# FEU31_Part2.net
KiCad netlist of a schematic drawn in Altium Designer
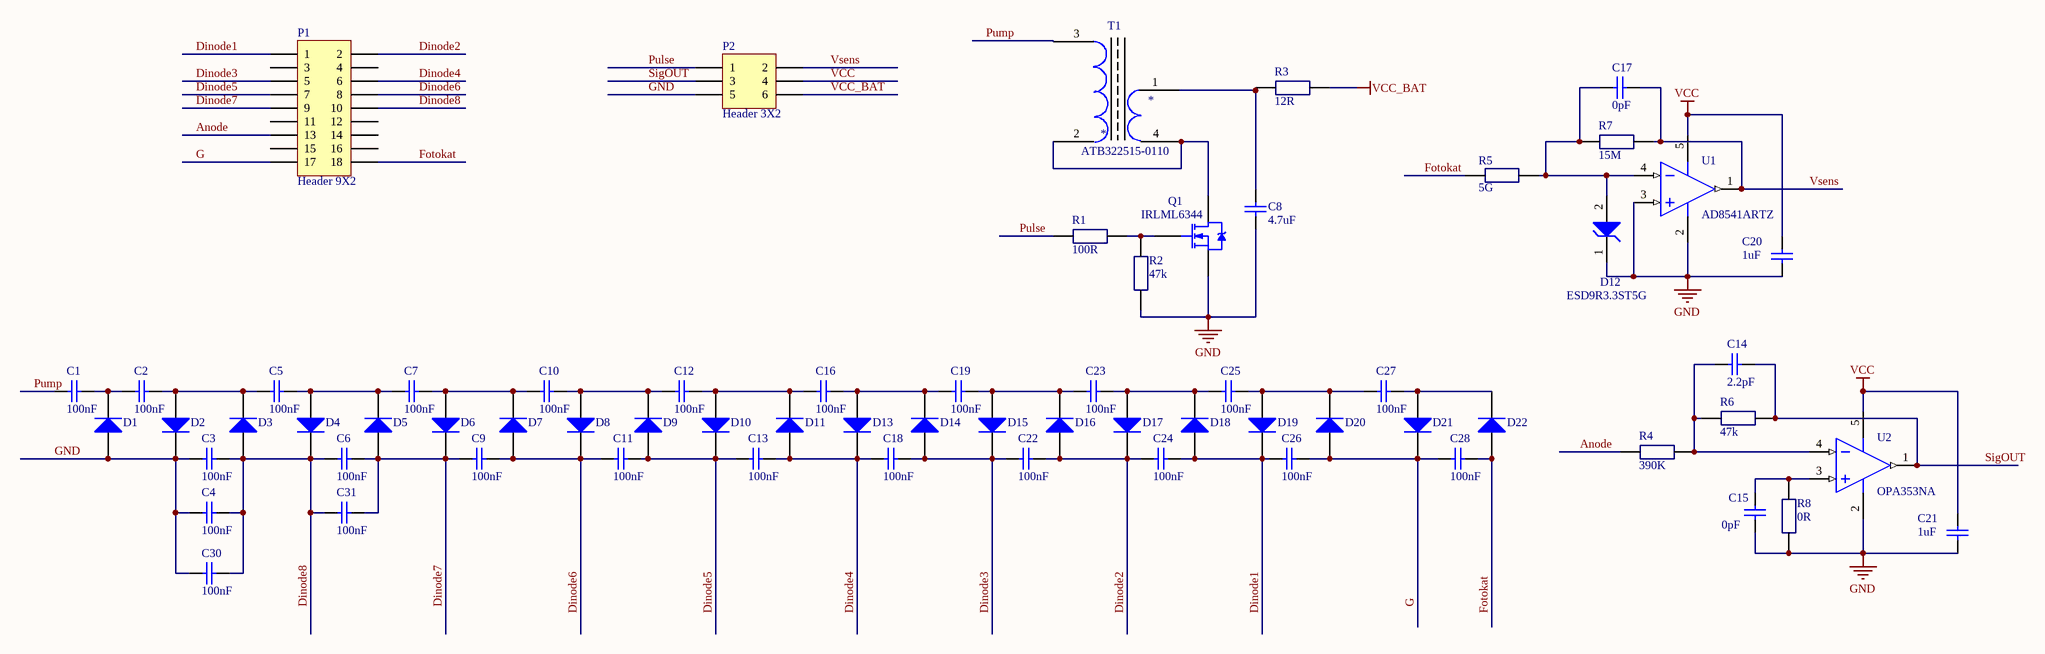
[diagram p0: FEU31_Part2.SchDoc]

(export (version "E")
  (design (tool "Eeschema 10.0.6"))
  (components
    (comp (ref "C1")
      (value "100nF")
      (footprint "Miscellaneous Devices:C1206")
      (description "Capacitor (Semiconductor SIM Model)")
      (fields (field (name "PUBLISHER") "Altium Limited"))
      (libsource (lib "Miscellaneous Devices") (part "Cap Semi"))
    )
    (comp (ref "C2")
      (value "100nF")
      (footprint "Miscellaneous Devices:C1206")
      (description "Capacitor (Semiconductor SIM Model)")
      (fields (field (name "PUBLISHER") "Altium Limited"))
      (libsource (lib "Miscellaneous Devices") (part "Cap Semi"))
    )
    (comp (ref "C3")
      (value "100nF")
      (footprint "Miscellaneous Devices:C1206")
      (description "Capacitor (Semiconductor SIM Model)")
      (fields (field (name "PUBLISHER") "Altium Limited"))
      (libsource (lib "Miscellaneous Devices") (part "Cap Semi"))
    )
    (comp (ref "C4")
      (value "100nF")
      (footprint "Miscellaneous Devices:C1206")
      (description "Capacitor (Semiconductor SIM Model)")
      (fields (field (name "PUBLISHER") "Altium Limited"))
      (libsource (lib "Miscellaneous Devices") (part "Cap Semi"))
    )
    (comp (ref "C5")
      (value "100nF")
      (footprint "Miscellaneous Devices:C1206")
      (description "Capacitor (Semiconductor SIM Model)")
      (fields (field (name "PUBLISHER") "Altium Limited"))
      (libsource (lib "Miscellaneous Devices") (part "Cap Semi"))
    )
    (comp (ref "C6")
      (value "100nF")
      (footprint "Miscellaneous Devices:C1206")
      (description "Capacitor (Semiconductor SIM Model)")
      (fields (field (name "PUBLISHER") "Altium Limited"))
      (libsource (lib "Miscellaneous Devices") (part "Cap Semi"))
    )
    (comp (ref "C7")
      (value "100nF")
      (footprint "Miscellaneous Devices:C1206")
      (description "Capacitor (Semiconductor SIM Model)")
      (fields (field (name "PUBLISHER") "Altium Limited"))
      (libsource (lib "Miscellaneous Devices") (part "Cap Semi"))
    )
    (comp (ref "C8")
      (value "4.7uF")
      (footprint "Miscellaneous Devices:C1206")
      (description "Capacitor (Semiconductor SIM Model)")
      (fields (field (name "PUBLISHER") "Altium Limited"))
      (libsource (lib "Miscellaneous Devices") (part "Cap Semi"))
    )
    (comp (ref "C9")
      (value "100nF")
      (footprint "Miscellaneous Devices:C1206")
      (description "Capacitor (Semiconductor SIM Model)")
      (fields (field (name "PUBLISHER") "Altium Limited"))
      (libsource (lib "Miscellaneous Devices") (part "Cap Semi"))
    )
    (comp (ref "C10")
      (value "100nF")
      (footprint "Miscellaneous Devices:C1206")
      (description "Capacitor (Semiconductor SIM Model)")
      (fields (field (name "PUBLISHER") "Altium Limited"))
      (libsource (lib "Miscellaneous Devices") (part "Cap Semi"))
    )
    (comp (ref "C11")
      (value "100nF")
      (footprint "Miscellaneous Devices:C1206")
      (description "Capacitor (Semiconductor SIM Model)")
      (fields (field (name "PUBLISHER") "Altium Limited"))
      (libsource (lib "Miscellaneous Devices") (part "Cap Semi"))
    )
    (comp (ref "C12")
      (value "100nF")
      (footprint "Miscellaneous Devices:C1206")
      (description "Capacitor (Semiconductor SIM Model)")
      (fields (field (name "PUBLISHER") "Altium Limited"))
      (libsource (lib "Miscellaneous Devices") (part "Cap Semi"))
    )
    (comp (ref "C13")
      (value "100nF")
      (footprint "Miscellaneous Devices:C1206")
      (description "Capacitor (Semiconductor SIM Model)")
      (fields (field (name "PUBLISHER") "Altium Limited"))
      (libsource (lib "Miscellaneous Devices") (part "Cap Semi"))
    )
    (comp (ref "C14")
      (value "2.2pF")
      (footprint "1608[0603]")
      (description "Capacitor (Semiconductor SIM Model)")
      (fields (field (name "PUBLISHER") "Altium Limited"))
      (libsource (lib "Miscellaneous Devices") (part "Cap Semi"))
    )
    (comp (ref "C15")
      (value "0pF")
      (footprint "1608[0603]_CAP")
      (description "Capacitor (Semiconductor SIM Model)")
      (fields (field (name "PUBLISHER") "Altium Limited"))
      (libsource (lib "Miscellaneous Devices") (part "Cap Semi"))
    )
    (comp (ref "C16")
      (value "100nF")
      (footprint "Miscellaneous Devices:C1206")
      (description "Capacitor (Semiconductor SIM Model)")
      (fields (field (name "PUBLISHER") "Altium Limited"))
      (libsource (lib "Miscellaneous Devices") (part "Cap Semi"))
    )
    (comp (ref "C17")
      (value "0pF")
      (footprint "1608[0603]")
      (description "Capacitor (Semiconductor SIM Model)")
      (fields (field (name "PUBLISHER") "Altium Limited"))
      (libsource (lib "Miscellaneous Devices") (part "Cap Semi"))
    )
    (comp (ref "C18")
      (value "100nF")
      (footprint "Miscellaneous Devices:C1206")
      (description "Capacitor (Semiconductor SIM Model)")
      (fields (field (name "PUBLISHER") "Altium Limited"))
      (libsource (lib "Miscellaneous Devices") (part "Cap Semi"))
    )
    (comp (ref "C19")
      (value "100nF")
      (footprint "Miscellaneous Devices:C1206")
      (description "Capacitor (Semiconductor SIM Model)")
      (fields (field (name "PUBLISHER") "Altium Limited"))
      (libsource (lib "Miscellaneous Devices") (part "Cap Semi"))
    )
    (comp (ref "C20")
      (value "1uF")
      (footprint "1608[0603]_CAP")
      (description "Capacitor (Semiconductor SIM Model)")
      (fields (field (name "PUBLISHER") "Altium Limited"))
      (libsource (lib "Miscellaneous Devices") (part "Cap Semi"))
    )
    (comp (ref "C21")
      (value "1uF")
      (footprint "1608[0603]_CAP")
      (description "Capacitor (Semiconductor SIM Model)")
      (fields (field (name "PUBLISHER") "Altium Limited"))
      (libsource (lib "Miscellaneous Devices") (part "Cap Semi"))
    )
    (comp (ref "C22")
      (value "100nF")
      (footprint "Miscellaneous Devices:C1206")
      (description "Capacitor (Semiconductor SIM Model)")
      (fields (field (name "PUBLISHER") "Altium Limited"))
      (libsource (lib "Miscellaneous Devices") (part "Cap Semi"))
    )
    (comp (ref "C23")
      (value "100nF")
      (footprint "Miscellaneous Devices:C1206")
      (description "Capacitor (Semiconductor SIM Model)")
      (fields (field (name "PUBLISHER") "Altium Limited"))
      (libsource (lib "Miscellaneous Devices") (part "Cap Semi"))
    )
    (comp (ref "C24")
      (value "100nF")
      (footprint "Miscellaneous Devices:C1206")
      (description "Capacitor (Semiconductor SIM Model)")
      (fields (field (name "PUBLISHER") "Altium Limited"))
      (libsource (lib "Miscellaneous Devices") (part "Cap Semi"))
    )
    (comp (ref "C25")
      (value "100nF")
      (footprint "Miscellaneous Devices:C1206")
      (description "Capacitor (Semiconductor SIM Model)")
      (fields (field (name "PUBLISHER") "Altium Limited"))
      (libsource (lib "Miscellaneous Devices") (part "Cap Semi"))
    )
    (comp (ref "C26")
      (value "100nF")
      (footprint "Miscellaneous Devices:C1206")
      (description "Capacitor (Semiconductor SIM Model)")
      (fields (field (name "PUBLISHER") "Altium Limited"))
      (libsource (lib "Miscellaneous Devices") (part "Cap Semi"))
    )
    (comp (ref "C27")
      (value "100nF")
      (footprint "Miscellaneous Devices:C1206")
      (description "Capacitor (Semiconductor SIM Model)")
      (fields (field (name "PUBLISHER") "Altium Limited"))
      (libsource (lib "Miscellaneous Devices") (part "Cap Semi"))
    )
    (comp (ref "C28")
      (value "100nF")
      (footprint "Miscellaneous Devices:C1206")
      (description "Capacitor (Semiconductor SIM Model)")
      (fields (field (name "PUBLISHER") "Altium Limited"))
      (libsource (lib "Miscellaneous Devices") (part "Cap Semi"))
    )
    (comp (ref "C30")
      (value "100nF")
      (footprint "Miscellaneous Devices:C1206")
      (description "Capacitor (Semiconductor SIM Model)")
      (fields (field (name "PUBLISHER") "Altium Limited"))
      (libsource (lib "Miscellaneous Devices") (part "Cap Semi"))
    )
    (comp (ref "C31")
      (value "100nF")
      (footprint "Miscellaneous Devices:C1206")
      (description "Capacitor (Semiconductor SIM Model)")
      (fields (field (name "PUBLISHER") "Altium Limited"))
      (libsource (lib "Miscellaneous Devices") (part "Cap Semi"))
    )
    (comp (ref "D1")
      (value "~")
      (footprint "DA2JF8100L")
      (description "Default Diode")
      (fields (field (name "PUBLISHER") "Altium Limited"))
      (libsource (lib "Miscellaneous Devices") (part "Diode"))
    )
    (comp (ref "D2")
      (value "~")
      (footprint "DA2JF8100L")
      (description "Default Diode")
      (fields (field (name "PUBLISHER") "Altium Limited"))
      (libsource (lib "Miscellaneous Devices") (part "Diode"))
    )
    (comp (ref "D3")
      (value "~")
      (footprint "DA2JF8100L")
      (description "Default Diode")
      (fields (field (name "PUBLISHER") "Altium Limited"))
      (libsource (lib "Miscellaneous Devices") (part "Diode"))
    )
    (comp (ref "D4")
      (value "~")
      (footprint "DA2JF8100L")
      (description "Default Diode")
      (fields (field (name "PUBLISHER") "Altium Limited"))
      (libsource (lib "Miscellaneous Devices") (part "Diode"))
    )
    (comp (ref "D5")
      (value "~")
      (footprint "DA2JF8100L")
      (description "Default Diode")
      (fields (field (name "PUBLISHER") "Altium Limited"))
      (libsource (lib "Miscellaneous Devices") (part "Diode"))
    )
    (comp (ref "D6")
      (value "~")
      (footprint "DA2JF8100L")
      (description "Default Diode")
      (fields (field (name "PUBLISHER") "Altium Limited"))
      (libsource (lib "Miscellaneous Devices") (part "Diode"))
    )
    (comp (ref "D7")
      (value "~")
      (footprint "DA2JF8100L")
      (description "Default Diode")
      (fields (field (name "PUBLISHER") "Altium Limited"))
      (libsource (lib "Miscellaneous Devices") (part "Diode"))
    )
    (comp (ref "D8")
      (value "~")
      (footprint "DA2JF8100L")
      (description "Default Diode")
      (fields (field (name "PUBLISHER") "Altium Limited"))
      (libsource (lib "Miscellaneous Devices") (part "Diode"))
    )
    (comp (ref "D9")
      (value "~")
      (footprint "DA2JF8100L")
      (description "Default Diode")
      (fields (field (name "PUBLISHER") "Altium Limited"))
      (libsource (lib "Miscellaneous Devices") (part "Diode"))
    )
    (comp (ref "D10")
      (value "~")
      (footprint "DA2JF8100L")
      (description "Default Diode")
      (fields (field (name "PUBLISHER") "Altium Limited"))
      (libsource (lib "Miscellaneous Devices") (part "Diode"))
    )
    (comp (ref "D11")
      (value "~")
      (footprint "DA2JF8100L")
      (description "Default Diode")
      (fields (field (name "PUBLISHER") "Altium Limited"))
      (libsource (lib "Miscellaneous Devices") (part "Diode"))
    )
    (comp (ref "D12")
      (value "ESD9R3.3ST5G")
      (footprint "ONSC-SOD-923-2-514AB-01_V")
      (fields (field (name "MANUFACTURER") "On Semiconductor"))
      (libsource (lib "ON Semi ESD Protection Diodes & Arrays") (part "ESD9R3.3ST5G"))
    )
    (comp (ref "D13")
      (value "~")
      (footprint "DA2JF8100L")
      (description "Default Diode")
      (fields (field (name "PUBLISHER") "Altium Limited"))
      (libsource (lib "Miscellaneous Devices") (part "Diode"))
    )
    (comp (ref "D14")
      (value "~")
      (footprint "DA2JF8100L")
      (description "Default Diode")
      (fields (field (name "PUBLISHER") "Altium Limited"))
      (libsource (lib "Miscellaneous Devices") (part "Diode"))
    )
    (comp (ref "D15")
      (value "~")
      (footprint "DA2JF8100L")
      (description "Default Diode")
      (fields (field (name "PUBLISHER") "Altium Limited"))
      (libsource (lib "Miscellaneous Devices") (part "Diode"))
    )
    (comp (ref "D16")
      (value "~")
      (footprint "DA2JF8100L")
      (description "Default Diode")
      (fields (field (name "PUBLISHER") "Altium Limited"))
      (libsource (lib "Miscellaneous Devices") (part "Diode"))
    )
    (comp (ref "D17")
      (value "~")
      (footprint "DA2JF8100L")
      (description "Default Diode")
      (fields (field (name "PUBLISHER") "Altium Limited"))
      (libsource (lib "Miscellaneous Devices") (part "Diode"))
    )
    (comp (ref "D18")
      (value "~")
      (footprint "DA2JF8100L")
      (description "Default Diode")
      (fields (field (name "PUBLISHER") "Altium Limited"))
      (libsource (lib "Miscellaneous Devices") (part "Diode"))
    )
    (comp (ref "D19")
      (value "~")
      (footprint "DA2JF8100L")
      (description "Default Diode")
      (fields (field (name "PUBLISHER") "Altium Limited"))
      (libsource (lib "Miscellaneous Devices") (part "Diode"))
    )
    (comp (ref "D20")
      (value "~")
      (footprint "DA2JF8100L")
      (description "Default Diode")
      (fields (field (name "PUBLISHER") "Altium Limited"))
      (libsource (lib "Miscellaneous Devices") (part "Diode"))
    )
    (comp (ref "D21")
      (value "~")
      (footprint "DA2JF8100L")
      (description "Default Diode")
      (fields (field (name "PUBLISHER") "Altium Limited"))
      (libsource (lib "Miscellaneous Devices") (part "Diode"))
    )
    (comp (ref "D22")
      (value "~")
      (footprint "DA2JF8100L")
      (description "Default Diode")
      (fields (field (name "PUBLISHER") "Altium Limited"))
      (libsource (lib "Miscellaneous Devices") (part "Diode"))
    )
    (comp (ref "P1")
      (value "Header 9X2")
      (footprint "R1306-19")
      (description "Header, 9-Pin, Dual row")
      (fields (field (name "PUBLISHER") "Altium Limited"))
      (libsource (lib "Miscellaneous Connectors") (part "Header 9X2"))
    )
    (comp (ref "P2")
      (value "Header 3X2")
      (footprint "HDR2X3")
      (description "Header, 3-Pin, Dual row")
      (fields (field (name "PUBLISHER") "Altium Limited"))
      (libsource (lib "Miscellaneous Connectors") (part "Header 3X2"))
    )
    (comp (ref "Q1")
      (value "IRLML6344")
      (footprint "SOT-23_N")
      (description "HEXFET Power MOSFET")
      (fields (field (name "PUBLISHER") "Altium Limited"))
      (libsource (lib "IR Discrete MOSFET - Power") (part "IRLML2402"))
    )
    (comp (ref "R1")
      (value "100R")
      (footprint "1608[0603]_RES")
      (libsource (lib "Микрон-3") (part "Resistor 0805"))
    )
    (comp (ref "R2")
      (value "47k")
      (footprint "1608[0603]_RES")
      (libsource (lib "Микрон-3") (part "Resistor 0805"))
    )
    (comp (ref "R3")
      (value "12R")
      (footprint "1608[0603]_RES")
      (libsource (lib "Микрон-3") (part "Resistor 0805"))
    )
    (comp (ref "R4")
      (value "390K")
      (footprint "1608[0603]_RES")
      (libsource (lib "Микрон-3") (part "Resistor 0805"))
    )
    (comp (ref "R5")
      (value "5G")
      (footprint "HVF2512T5007FE")
      (libsource (lib "Микрон-3") (part "Resistor 0805"))
    )
    (comp (ref "R6")
      (value "47k")
      (footprint "1608[0603]_RES")
      (libsource (lib "Микрон-3") (part "Resistor 0805"))
    )
    (comp (ref "R7")
      (value "15M")
      (footprint "1608[0603]_RES")
      (libsource (lib "Микрон-3") (part "Resistor 0805"))
    )
    (comp (ref "R8")
      (value "0R")
      (footprint "1608[0603]_RES")
      (libsource (lib "Микрон-3") (part "Resistor 0805"))
    )
    (comp (ref "T1")
      (value "ATB322515-0110")
      (footprint "ATB322515-0110")
      (libsource (lib "My SCH library") (part "ATB322515-0110"))
    )
    (comp (ref "U1")
      (value "AD8541ARTZ")
      (footprint "ADI-RJ-5_N")
      (fields
        (field (name "GENERIC PART NUMBER") "AD8541")
        (field (name "MANUFACTURER") "Analog Devices")
        (field (name "PARTNUMBER") "AD8541ARTZ-R2")
      )
      (libsource (lib "Analog Devices Operational Amplifiers") (part "AD8541ARTZ-R2"))
    )
    (comp (ref "U2")
      (value "OPA353NA")
      (footprint "ADI-RJ-5_N")
      (fields
        (field (name "GENERIC PART NUMBER") "AD8541")
        (field (name "MANUFACTURER") "Analog Devices")
        (field (name "PARTNUMBER") "AD8541ARTZ-R2")
      )
      (libsource (lib "Analog Devices Operational Amplifiers") (part "AD8541ARTZ-R2"))
    )
  )
  (nets
    (net (code "1") (name "/Anode") (class "Default")
      (node (ref "P1") (pin "13") (pinfunction "13_13") (pintype "passive"))
      (node (ref "R4") (pin "2") (pinfunction "2_2") (pintype "passive"))
    )
    (net (code "2") (name "/Dinode1") (class "Default")
      (node (ref "C24") (pin "1") (pinfunction "1_1") (pintype "passive"))
      (node (ref "C26") (pin "2") (pinfunction "2_2") (pintype "passive"))
      (node (ref "D18") (pin "1") (pinfunction "A_1") (pintype "passive"))
      (node (ref "D19") (pin "2") (pinfunction "K_2") (pintype "passive"))
      (node (ref "P1") (pin "1") (pinfunction "1_1") (pintype "passive"))
    )
    (net (code "3") (name "/Dinode2") (class "Default")
      (node (ref "C22") (pin "1") (pinfunction "1_1") (pintype "passive"))
      (node (ref "C24") (pin "2") (pinfunction "2_2") (pintype "passive"))
      (node (ref "D16") (pin "1") (pinfunction "A_1") (pintype "passive"))
      (node (ref "D17") (pin "2") (pinfunction "K_2") (pintype "passive"))
      (node (ref "P1") (pin "2") (pinfunction "2_2") (pintype "passive"))
    )
    (net (code "4") (name "/Dinode3") (class "Default")
      (node (ref "C18") (pin "1") (pinfunction "1_1") (pintype "passive"))
      (node (ref "C22") (pin "2") (pinfunction "2_2") (pintype "passive"))
      (node (ref "D14") (pin "1") (pinfunction "A_1") (pintype "passive"))
      (node (ref "D15") (pin "2") (pinfunction "K_2") (pintype "passive"))
      (node (ref "P1") (pin "5") (pinfunction "5_5") (pintype "passive"))
    )
    (net (code "5") (name "/Dinode4") (class "Default")
      (node (ref "C13") (pin "1") (pinfunction "1_1") (pintype "passive"))
      (node (ref "C18") (pin "2") (pinfunction "2_2") (pintype "passive"))
      (node (ref "D11") (pin "1") (pinfunction "A_1") (pintype "passive"))
      (node (ref "D13") (pin "2") (pinfunction "K_2") (pintype "passive"))
      (node (ref "P1") (pin "6") (pinfunction "6_6") (pintype "passive"))
    )
    (net (code "6") (name "/Dinode5") (class "Default")
      (node (ref "C11") (pin "1") (pinfunction "1_1") (pintype "passive"))
      (node (ref "C13") (pin "2") (pinfunction "2_2") (pintype "passive"))
      (node (ref "D10") (pin "2") (pinfunction "K_2") (pintype "passive"))
      (node (ref "D9") (pin "1") (pinfunction "A_1") (pintype "passive"))
      (node (ref "P1") (pin "7") (pinfunction "7_7") (pintype "passive"))
    )
    (net (code "7") (name "/Dinode6") (class "Default")
      (node (ref "C11") (pin "2") (pinfunction "2_2") (pintype "passive"))
      (node (ref "C9") (pin "1") (pinfunction "1_1") (pintype "passive"))
      (node (ref "D7") (pin "1") (pinfunction "A_1") (pintype "passive"))
      (node (ref "D8") (pin "2") (pinfunction "K_2") (pintype "passive"))
      (node (ref "P1") (pin "8") (pinfunction "8_8") (pintype "passive"))
    )
    (net (code "8") (name "/Dinode7") (class "Default")
      (node (ref "C31") (pin "1") (pinfunction "1_1") (pintype "passive"))
      (node (ref "C6") (pin "1") (pinfunction "1_1") (pintype "passive"))
      (node (ref "C9") (pin "2") (pinfunction "2_2") (pintype "passive"))
      (node (ref "D5") (pin "1") (pinfunction "A_1") (pintype "passive"))
      (node (ref "D6") (pin "2") (pinfunction "K_2") (pintype "passive"))
      (node (ref "P1") (pin "9") (pinfunction "9_9") (pintype "passive"))
    )
    (net (code "9") (name "/Dinode8") (class "Default")
      (node (ref "C3") (pin "1") (pinfunction "1_1") (pintype "passive"))
      (node (ref "C30") (pin "1") (pinfunction "1_1") (pintype "passive"))
      (node (ref "C31") (pin "2") (pinfunction "2_2") (pintype "passive"))
      (node (ref "C4") (pin "1") (pinfunction "1_1") (pintype "passive"))
      (node (ref "C6") (pin "2") (pinfunction "2_2") (pintype "passive"))
      (node (ref "D3") (pin "1") (pinfunction "A_1") (pintype "passive"))
      (node (ref "D4") (pin "2") (pinfunction "K_2") (pintype "passive"))
      (node (ref "P1") (pin "10") (pinfunction "10_10") (pintype "passive"))
    )
    (net (code "10") (name "/Fotokat") (class "Default")
      (node (ref "C28") (pin "1") (pinfunction "1_1") (pintype "passive"))
      (node (ref "D22") (pin "1") (pinfunction "A_1") (pintype "passive"))
      (node (ref "P1") (pin "18") (pinfunction "18_18") (pintype "passive"))
      (node (ref "R5") (pin "1") (pinfunction "A_1") (pintype "passive"))
    )
    (net (code "11") (name "/G") (class "Default")
      (node (ref "C26") (pin "1") (pinfunction "1_1") (pintype "passive"))
      (node (ref "C28") (pin "2") (pinfunction "2_2") (pintype "passive"))
      (node (ref "D20") (pin "1") (pinfunction "A_1") (pintype "passive"))
      (node (ref "D21") (pin "2") (pinfunction "K_2") (pintype "passive"))
      (node (ref "P1") (pin "17") (pinfunction "17_17") (pintype "passive"))
    )
    (net (code "12") (name "/Pulse") (class "Default")
      (node (ref "P2") (pin "1") (pinfunction "1_1") (pintype "passive"))
      (node (ref "R1") (pin "1") (pinfunction "A_1") (pintype "passive"))
    )
    (net (code "13") (name "/Pump") (class "Default")
      (node (ref "C1") (pin "2") (pinfunction "2_2") (pintype "passive"))
      (node (ref "T1") (pin "3") (pinfunction "3_3") (pintype "passive"))
    )
    (net (code "14") (name "/SigOUT") (class "Default")
      (node (ref "C14") (pin "2") (pinfunction "2_2") (pintype "passive"))
      (node (ref "P2") (pin "3") (pinfunction "3_3") (pintype "passive"))
      (node (ref "R6") (pin "2") (pinfunction "2_2") (pintype "passive"))
      (node (ref "U2") (pin "1") (pinfunction "OUT_A_1") (pintype "output"))
    )
    (net (code "15") (name "/Vsens") (class "Default")
      (node (ref "C17") (pin "2") (pinfunction "2_2") (pintype "passive"))
      (node (ref "P2") (pin "2") (pinfunction "2_2") (pintype "passive"))
      (node (ref "R7") (pin "2") (pinfunction "2_2") (pintype "passive"))
      (node (ref "U1") (pin "1") (pinfunction "OUT_A_1") (pintype "output"))
    )
    (net (code "16") (name "GND") (class "Default")
      (node (ref "C15") (pin "2") (pinfunction "2_2") (pintype "passive"))
      (node (ref "C20") (pin "2") (pinfunction "2_2") (pintype "passive"))
      (node (ref "C21") (pin "2") (pinfunction "2_2") (pintype "passive"))
      (node (ref "C3") (pin "2") (pinfunction "2_2") (pintype "passive"))
      (node (ref "C30") (pin "2") (pinfunction "2_2") (pintype "passive"))
      (node (ref "C4") (pin "2") (pinfunction "2_2") (pintype "passive"))
      (node (ref "C8") (pin "2") (pinfunction "2_2") (pintype "passive"))
      (node (ref "D1") (pin "1") (pinfunction "A_1") (pintype "passive"))
      (node (ref "D12") (pin "1") (pinfunction "K_1") (pintype "passive"))
      (node (ref "D2") (pin "2") (pinfunction "K_2") (pintype "passive"))
      (node (ref "P2") (pin "5") (pinfunction "5_5") (pintype "passive"))
      (node (ref "Q1") (pin "2") (pinfunction "S_2") (pintype "passive"))
      (node (ref "R2") (pin "1") (pinfunction "A_1") (pintype "passive"))
      (node (ref "R8") (pin "1") (pinfunction "A_1") (pintype "passive"))
      (node (ref "U1") (pin "2") (pinfunction "-V_2") (pintype "power_in"))
      (node (ref "U1") (pin "3") (pinfunction "+IN_A_3") (pintype "input"))
      (node (ref "U2") (pin "2") (pinfunction "-V_2") (pintype "power_in"))
    )
    (net (code "17") (name "Net-(D1-K)") (class "Default")
      (node (ref "C1") (pin "1") (pinfunction "1_1") (pintype "passive"))
      (node (ref "C2") (pin "2") (pinfunction "2_2") (pintype "passive"))
      (node (ref "D1") (pin "2") (pinfunction "K_2") (pintype "passive"))
    )
    (net (code "18") (name "Net-(D2-A)") (class "Default")
      (node (ref "C2") (pin "1") (pinfunction "1_1") (pintype "passive"))
      (node (ref "C5") (pin "2") (pinfunction "2_2") (pintype "passive"))
      (node (ref "D2") (pin "1") (pinfunction "A_1") (pintype "passive"))
      (node (ref "D3") (pin "2") (pinfunction "K_2") (pintype "passive"))
    )
    (net (code "19") (name "Net-(D4-A)") (class "Default")
      (node (ref "C5") (pin "1") (pinfunction "1_1") (pintype "passive"))
      (node (ref "C7") (pin "2") (pinfunction "2_2") (pintype "passive"))
      (node (ref "D4") (pin "1") (pinfunction "A_1") (pintype "passive"))
      (node (ref "D5") (pin "2") (pinfunction "K_2") (pintype "passive"))
    )
    (net (code "20") (name "Net-(D6-A)") (class "Default")
      (node (ref "C10") (pin "2") (pinfunction "2_2") (pintype "passive"))
      (node (ref "C7") (pin "1") (pinfunction "1_1") (pintype "passive"))
      (node (ref "D6") (pin "1") (pinfunction "A_1") (pintype "passive"))
      (node (ref "D7") (pin "2") (pinfunction "K_2") (pintype "passive"))
    )
    (net (code "21") (name "Net-(D8-A)") (class "Default")
      (node (ref "C10") (pin "1") (pinfunction "1_1") (pintype "passive"))
      (node (ref "C12") (pin "2") (pinfunction "2_2") (pintype "passive"))
      (node (ref "D8") (pin "1") (pinfunction "A_1") (pintype "passive"))
      (node (ref "D9") (pin "2") (pinfunction "K_2") (pintype "passive"))
    )
    (net (code "22") (name "Net-(D10-A)") (class "Default")
      (node (ref "C12") (pin "1") (pinfunction "1_1") (pintype "passive"))
      (node (ref "C16") (pin "2") (pinfunction "2_2") (pintype "passive"))
      (node (ref "D10") (pin "1") (pinfunction "A_1") (pintype "passive"))
      (node (ref "D11") (pin "2") (pinfunction "K_2") (pintype "passive"))
    )
    (net (code "23") (name "Net-(D12-A)") (class "Default")
      (node (ref "C17") (pin "1") (pinfunction "1_1") (pintype "passive"))
      (node (ref "D12") (pin "2") (pinfunction "A_2") (pintype "passive"))
      (node (ref "R5") (pin "2") (pinfunction "2_2") (pintype "passive"))
      (node (ref "R7") (pin "1") (pinfunction "A_1") (pintype "passive"))
      (node (ref "U1") (pin "4") (pinfunction "-IN_A_4") (pintype "input"))
    )
    (net (code "24") (name "Net-(D13-A)") (class "Default")
      (node (ref "C16") (pin "1") (pinfunction "1_1") (pintype "passive"))
      (node (ref "C19") (pin "2") (pinfunction "2_2") (pintype "passive"))
      (node (ref "D13") (pin "1") (pinfunction "A_1") (pintype "passive"))
      (node (ref "D14") (pin "2") (pinfunction "K_2") (pintype "passive"))
    )
    (net (code "25") (name "Net-(D15-A)") (class "Default")
      (node (ref "C19") (pin "1") (pinfunction "1_1") (pintype "passive"))
      (node (ref "C23") (pin "2") (pinfunction "2_2") (pintype "passive"))
      (node (ref "D15") (pin "1") (pinfunction "A_1") (pintype "passive"))
      (node (ref "D16") (pin "2") (pinfunction "K_2") (pintype "passive"))
    )
    (net (code "26") (name "Net-(D17-A)") (class "Default")
      (node (ref "C23") (pin "1") (pinfunction "1_1") (pintype "passive"))
      (node (ref "C25") (pin "2") (pinfunction "2_2") (pintype "passive"))
      (node (ref "D17") (pin "1") (pinfunction "A_1") (pintype "passive"))
      (node (ref "D18") (pin "2") (pinfunction "K_2") (pintype "passive"))
    )
    (net (code "27") (name "Net-(D19-A)") (class "Default")
      (node (ref "C25") (pin "1") (pinfunction "1_1") (pintype "passive"))
      (node (ref "C27") (pin "2") (pinfunction "2_2") (pintype "passive"))
      (node (ref "D19") (pin "1") (pinfunction "A_1") (pintype "passive"))
      (node (ref "D20") (pin "2") (pinfunction "K_2") (pintype "passive"))
    )
    (net (code "28") (name "Net-(D21-A)") (class "Default")
      (node (ref "C27") (pin "1") (pinfunction "1_1") (pintype "passive"))
      (node (ref "D21") (pin "1") (pinfunction "A_1") (pintype "passive"))
      (node (ref "D22") (pin "2") (pinfunction "K_2") (pintype "passive"))
    )
    (net (code "29") (name "Net-(Q1-D)") (class "Default")
      (node (ref "Q1") (pin "3") (pinfunction "D_3") (pintype "passive"))
      (node (ref "T1") (pin "2") (pinfunction "2_2") (pintype "passive"))
      (node (ref "T1") (pin "4") (pintype "passive"))
    )
    (net (code "30") (name "Net-(Q1-G)") (class "Default")
      (node (ref "Q1") (pin "1") (pinfunction "G_1") (pintype "passive"))
      (node (ref "R1") (pin "2") (pinfunction "2_2") (pintype "passive"))
      (node (ref "R2") (pin "2") (pinfunction "2_2") (pintype "passive"))
    )
    (net (code "31") (name "Net-(R3-A)") (class "Default")
      (node (ref "C8") (pin "1") (pinfunction "1_1") (pintype "passive"))
      (node (ref "R3") (pin "1") (pinfunction "A_1") (pintype "passive"))
      (node (ref "T1") (pin "1") (pinfunction "1_1") (pintype "passive"))
    )
    (net (code "32") (name "Net-(R4-A)") (class "Default")
      (node (ref "C14") (pin "1") (pinfunction "1_1") (pintype "passive"))
      (node (ref "R4") (pin "1") (pinfunction "A_1") (pintype "passive"))
      (node (ref "R6") (pin "1") (pinfunction "A_1") (pintype "passive"))
      (node (ref "U2") (pin "4") (pinfunction "-IN_A_4") (pintype "input"))
    )
    (net (code "33") (name "Net-(U2-+IN_A)") (class "Default")
      (node (ref "C15") (pin "1") (pinfunction "1_1") (pintype "passive"))
      (node (ref "R8") (pin "2") (pinfunction "2_2") (pintype "passive"))
      (node (ref "U2") (pin "3") (pinfunction "+IN_A_3") (pintype "input"))
    )
    (net (code "34") (name "VCC") (class "Default")
      (node (ref "C20") (pin "1") (pinfunction "1_1") (pintype "passive"))
      (node (ref "C21") (pin "1") (pinfunction "1_1") (pintype "passive"))
      (node (ref "P2") (pin "4") (pinfunction "4_4") (pintype "passive"))
      (node (ref "U1") (pin "5") (pinfunction "+V_5") (pintype "power_in"))
      (node (ref "U2") (pin "5") (pinfunction "+V_5") (pintype "power_in"))
    )
    (net (code "35") (name "VCC_BAT") (class "Default")
      (node (ref "P2") (pin "6") (pinfunction "6_6") (pintype "passive"))
      (node (ref "R3") (pin "2") (pinfunction "2_2") (pintype "passive"))
    )
    (net (code "36") (name "unconnected-(P1-Pad3)") (class "Default")
      (node (ref "P1") (pin "3") (pinfunction "3_3") (pintype "passive"))
    )
    (net (code "37") (name "unconnected-(P1-Pad4)") (class "Default")
      (node (ref "P1") (pin "4") (pinfunction "4_4") (pintype "passive"))
    )
    (net (code "38") (name "unconnected-(P1-Pad11)") (class "Default")
      (node (ref "P1") (pin "11") (pinfunction "11_11") (pintype "passive"))
    )
    (net (code "39") (name "unconnected-(P1-Pad12)") (class "Default")
      (node (ref "P1") (pin "12") (pinfunction "12_12") (pintype "passive"))
    )
    (net (code "40") (name "unconnected-(P1-Pad14)") (class "Default")
      (node (ref "P1") (pin "14") (pinfunction "14_14") (pintype "passive"))
    )
    (net (code "41") (name "unconnected-(P1-Pad15)") (class "Default")
      (node (ref "P1") (pin "15") (pinfunction "15_15") (pintype "passive"))
    )
    (net (code "42") (name "unconnected-(P1-Pad16)") (class "Default")
      (node (ref "P1") (pin "16") (pinfunction "16_16") (pintype "passive"))
    )
  )
)
